# MPR121-Cap-Touch-Keypad.net
KiCad netlist of a schematic drawn in EAGLE
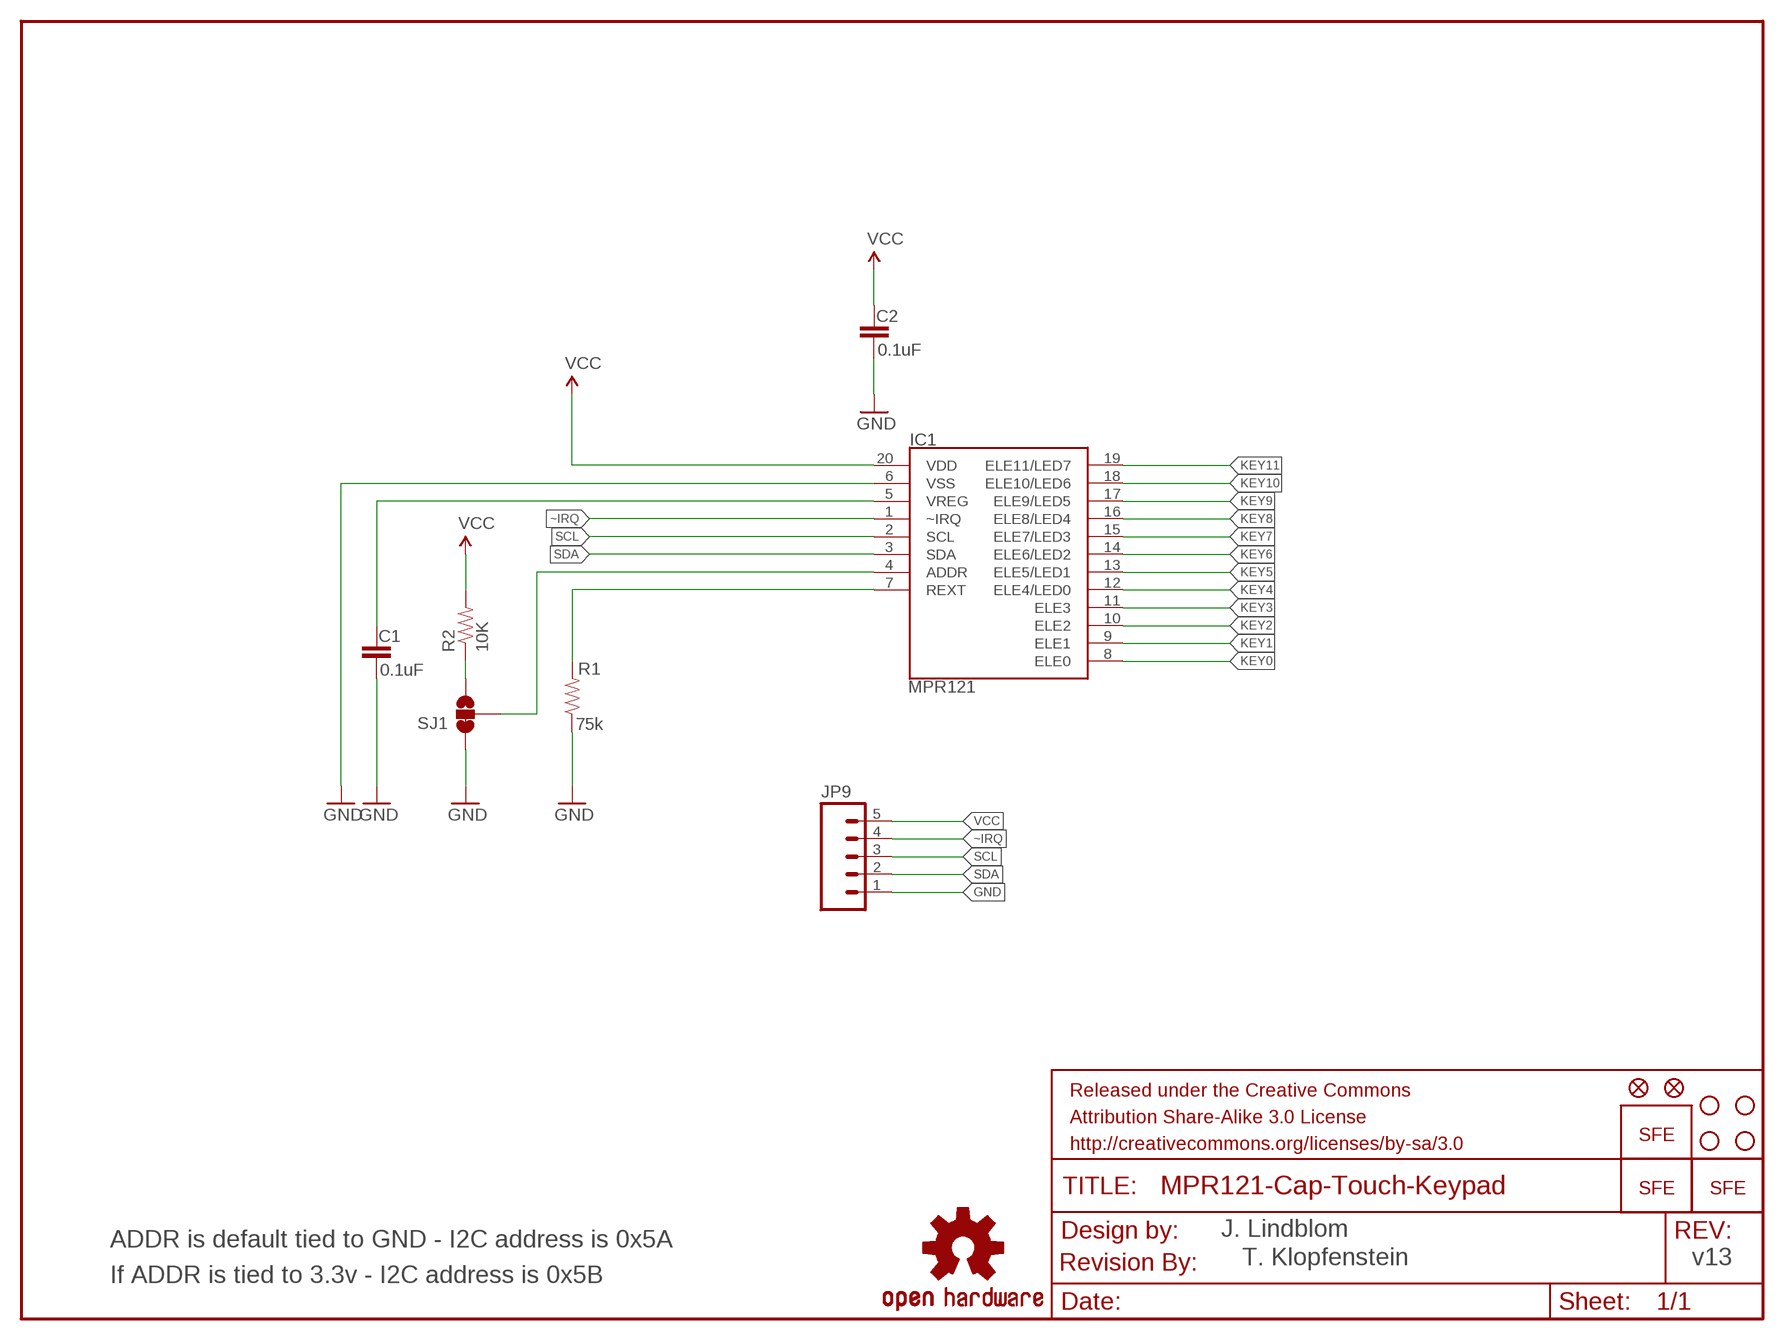
[diagram p0: schematic, sheet 1]

(export (version "E")
  (design (tool "Eeschema 10.0.6"))
  (components
    (comp (ref "C1")
      (value "0.1uF")
      (footprint "eagle-import:0603-CAP")
      (libsource (lib "eagle-import") (part "CAP0603-CAP"))
    )
    (comp (ref "C2")
      (value "0.1uF")
      (footprint "eagle-import:0603-CAP")
      (libsource (lib "eagle-import") (part "CAP0603-CAP"))
    )
    (comp (ref "FRAME1")
      (value "FRAME-LETTER")
      (footprint "eagle-import:CREATIVE_COMMONS")
      (libsource (lib "eagle-import") (part "FRAME-LETTER"))
    )
    (comp (ref "IC1")
      (value "MPR121")
      (footprint "eagle-import:QFN-20-0.4MM-V2")
      (libsource (lib "eagle-import") (part "MPR121V2"))
    )
    (comp (ref "JP1")
      (value "LOGO-SFENEW")
      (footprint "eagle-import:SFE-NEW-WEBLOGO")
      (libsource (lib "eagle-import") (part "LOGO-SFENEW"))
    )
    (comp (ref "JP2")
      (value "LOGO-SFESK")
      (footprint "eagle-import:SFE-LOGO-FLAME")
      (libsource (lib "eagle-import") (part "LOGO-SFESK"))
    )
    (comp (ref "JP3")
      (value "STAND-OFF")
      (footprint "eagle-import:STAND-OFF")
      (libsource (lib "eagle-import") (part "STAND-OFF"))
    )
    (comp (ref "JP4")
      (value "STAND-OFF")
      (footprint "eagle-import:STAND-OFF")
      (libsource (lib "eagle-import") (part "STAND-OFF"))
    )
    (comp (ref "JP5")
      (value "FIDUCIAL1X2")
      (footprint "eagle-import:FIDUCIAL-1X2")
      (libsource (lib "eagle-import") (part "FIDUCIAL1X2"))
    )
    (comp (ref "JP6")
      (value "LOGO-SFESK")
      (footprint "eagle-import:SFE-LOGO-FLAME")
      (libsource (lib "eagle-import") (part "LOGO-SFESK"))
    )
    (comp (ref "JP7")
      (value "STAND-OFF")
      (footprint "eagle-import:STAND-OFF")
      (libsource (lib "eagle-import") (part "STAND-OFF"))
    )
    (comp (ref "JP8")
      (value "STAND-OFF")
      (footprint "eagle-import:STAND-OFF")
      (libsource (lib "eagle-import") (part "STAND-OFF"))
    )
    (comp (ref "JP9")
      (value "M05PTH")
      (footprint "eagle-import:1X05")
      (libsource (lib "eagle-import") (part "M05PTH"))
    )
    (comp (ref "JP10")
      (value "FIDUCIAL1X2")
      (footprint "eagle-import:FIDUCIAL-1X2")
      (libsource (lib "eagle-import") (part "FIDUCIAL1X2"))
    )
    (comp (ref "LOGO1")
      (value "OSHW-LOGOL")
      (footprint "eagle-import:OSHW-LOGO-L")
      (libsource (lib "eagle-import") (part "OSHW-LOGOL"))
    )
    (comp (ref "R1")
      (value "75k")
      (footprint "eagle-import:0603-RES")
      (libsource (lib "eagle-import") (part "RESISTOR0603-RES"))
    )
    (comp (ref "R2")
      (value "10K")
      (footprint "eagle-import:0603-RES")
      (libsource (lib "eagle-import") (part "10KOHM1/10W1%(0603)0603"))
    )
    (comp (ref "SJ1")
      (value "SOLDERJUMPER_2WAYPASTE1&2")
      (footprint "eagle-import:SJ_3_PASTE1&2")
      (libsource (lib "eagle-import") (part "SOLDERJUMPER_2WAYPASTE1&2"))
    )
    (comp (ref "U$1")
      (value "REVISION")
      (footprint "eagle-import:REVISION")
      (libsource (lib "eagle-import") (part "REVISION"))
    )
  )
  (nets
    (net (code "1") (name "/~{IRQ}") (class "Default")
      (node (ref "IC1") (pin "1") (pinfunction "~{IRQ}_1") (pintype "bidirectional"))
      (node (ref "JP9") (pin "4") (pinfunction "4_4") (pintype "passive"))
    )
    (net (code "2") (name "GND") (class "Default")
      (node (ref "C1") (pin "2") (pinfunction "2_2") (pintype "passive"))
      (node (ref "C2") (pin "2") (pinfunction "2_2") (pintype "passive"))
      (node (ref "IC1") (pin "6") (pinfunction "VSS_6") (pintype "bidirectional"))
      (node (ref "JP9") (pin "1") (pinfunction "1_1") (pintype "passive"))
      (node (ref "R1") (pin "1") (pinfunction "1_1") (pintype "passive"))
      (node (ref "SJ1") (pin "1") (pinfunction "1_1") (pintype "passive"))
    )
    (net (code "3") (name "KEY0") (class "Default")
      (node (ref "IC1") (pin "8") (pinfunction "ELE0_8") (pintype "bidirectional"))
    )
    (net (code "4") (name "KEY1") (class "Default")
      (node (ref "IC1") (pin "9") (pinfunction "ELE1_9") (pintype "bidirectional"))
    )
    (net (code "5") (name "KEY2") (class "Default")
      (node (ref "IC1") (pin "10") (pinfunction "ELE2_10") (pintype "bidirectional"))
    )
    (net (code "6") (name "KEY3") (class "Default")
      (node (ref "IC1") (pin "11") (pinfunction "ELE3_11") (pintype "bidirectional"))
    )
    (net (code "7") (name "KEY4") (class "Default")
      (node (ref "IC1") (pin "12") (pinfunction "ELE4/LED0_12") (pintype "bidirectional"))
    )
    (net (code "8") (name "KEY5") (class "Default")
      (node (ref "IC1") (pin "13") (pinfunction "ELE5/LED1_13") (pintype "bidirectional"))
    )
    (net (code "9") (name "KEY6") (class "Default")
      (node (ref "IC1") (pin "14") (pinfunction "ELE6/LED2_14") (pintype "bidirectional"))
    )
    (net (code "10") (name "KEY7") (class "Default")
      (node (ref "IC1") (pin "15") (pinfunction "ELE7/LED3_15") (pintype "bidirectional"))
    )
    (net (code "11") (name "KEY8") (class "Default")
      (node (ref "IC1") (pin "16") (pinfunction "ELE8/LED4_16") (pintype "bidirectional"))
    )
    (net (code "12") (name "KEY9") (class "Default")
      (node (ref "IC1") (pin "17") (pinfunction "ELE9/LED5_17") (pintype "bidirectional"))
    )
    (net (code "13") (name "KEY10") (class "Default")
      (node (ref "IC1") (pin "18") (pinfunction "ELE10/LED6_18") (pintype "bidirectional"))
    )
    (net (code "14") (name "KEY11") (class "Default")
      (node (ref "IC1") (pin "19") (pinfunction "ELE11/LED7_19") (pintype "bidirectional"))
    )
    (net (code "15") (name "Net-(IC1-ADDR)") (class "Default")
      (node (ref "IC1") (pin "4") (pinfunction "ADDR_4") (pintype "bidirectional"))
      (node (ref "SJ1") (pin "2") (pinfunction "2_2") (pintype "passive"))
    )
    (net (code "16") (name "Net-(IC1-REXT)") (class "Default")
      (node (ref "IC1") (pin "7") (pinfunction "REXT_7") (pintype "bidirectional"))
      (node (ref "R1") (pin "2") (pinfunction "2_2") (pintype "passive"))
    )
    (net (code "17") (name "Net-(IC1-VREG)") (class "Default")
      (node (ref "C1") (pin "1") (pinfunction "1_1") (pintype "passive"))
      (node (ref "IC1") (pin "5") (pinfunction "VREG_5") (pintype "bidirectional"))
    )
    (net (code "18") (name "Net-(R2-Pad1)") (class "Default")
      (node (ref "R2") (pin "1") (pinfunction "1_1") (pintype "passive"))
      (node (ref "SJ1") (pin "3") (pinfunction "3_3") (pintype "passive"))
    )
    (net (code "19") (name "SCL") (class "Default")
      (node (ref "IC1") (pin "2") (pinfunction "SCL_2") (pintype "bidirectional"))
      (node (ref "JP9") (pin "3") (pinfunction "3_3") (pintype "passive"))
    )
    (net (code "20") (name "SDA") (class "Default")
      (node (ref "IC1") (pin "3") (pinfunction "SDA_3") (pintype "bidirectional"))
      (node (ref "JP9") (pin "2") (pinfunction "2_2") (pintype "passive"))
    )
    (net (code "21") (name "VCC") (class "Default")
      (node (ref "C2") (pin "1") (pinfunction "1_1") (pintype "passive"))
      (node (ref "IC1") (pin "20") (pinfunction "VDD_20") (pintype "bidirectional"))
      (node (ref "JP9") (pin "5") (pinfunction "5_5") (pintype "passive"))
      (node (ref "R2") (pin "2") (pinfunction "2_2") (pintype "passive"))
    )
  )
)
